# squall-blees-board.net
KiCad netlist of a schematic drawn in EAGLE
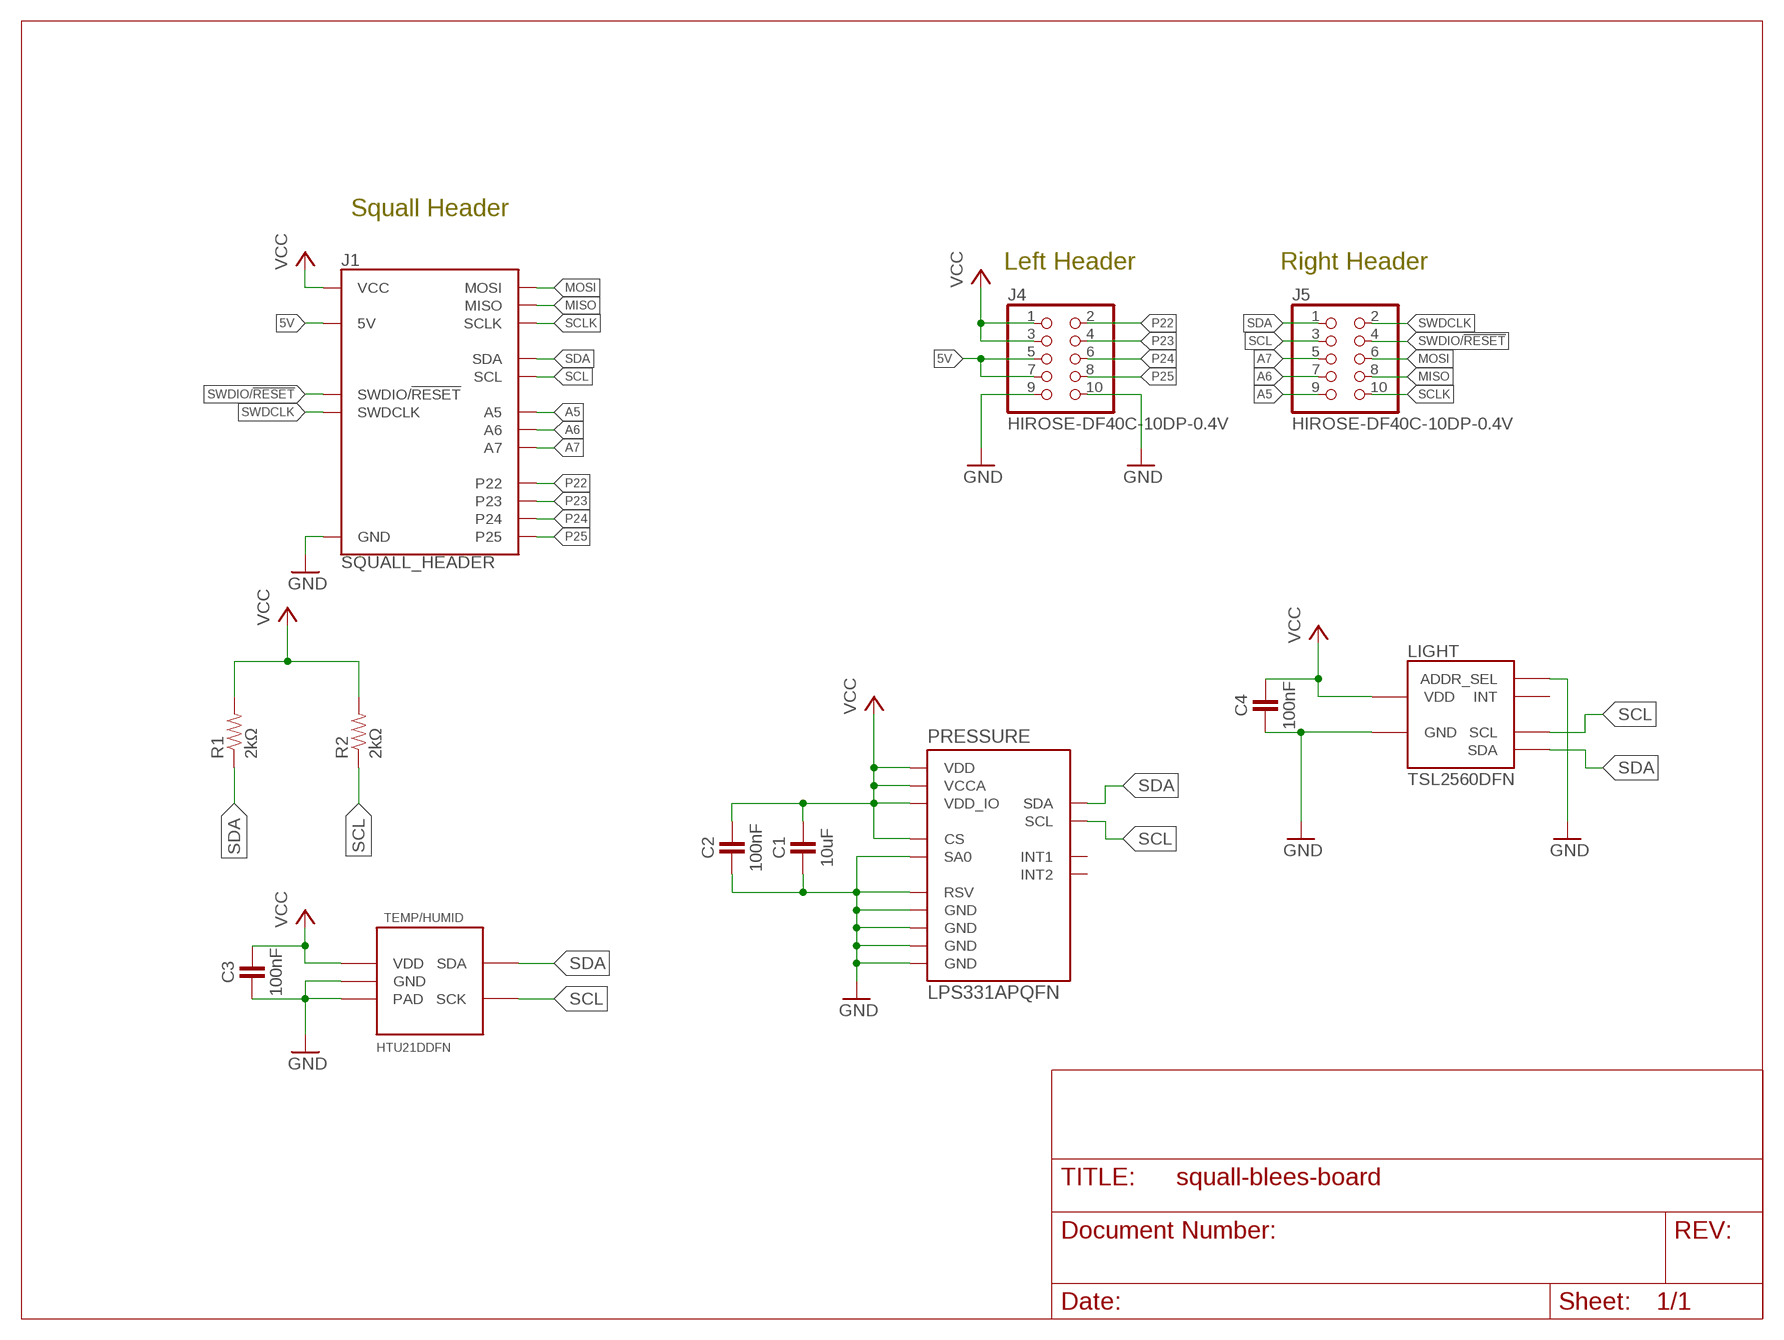
[diagram p0: schematic, sheet 1]

(export (version "E")
  (design (tool "Eeschema 10.0.6"))
  (components
    (comp (ref "C1")
      (value "10uF")
      (footprint "eagle-import:0603_CAP")
      (libsource (lib "eagle-import") (part "CAPACITOR0603_CAP"))
    )
    (comp (ref "C2")
      (value "100nF")
      (footprint "eagle-import:0402_CAP")
      (libsource (lib "eagle-import") (part "CAPACITOR"))
    )
    (comp (ref "C3")
      (value "100nF")
      (footprint "eagle-import:0402_CAP")
      (libsource (lib "eagle-import") (part "CAPACITOR"))
    )
    (comp (ref "C4")
      (value "100nF")
      (footprint "eagle-import:0402_CAP")
      (libsource (lib "eagle-import") (part "CAPACITOR"))
    )
    (comp (ref "J1")
      (value "SQUALL_HEADER")
      (footprint "eagle-import:SQUALL_HEADER")
      (libsource (lib "eagle-import") (part "SQUALL_HEADER"))
    )
    (comp (ref "J4")
      (value "HIROSE-DF40C-10DP-0.4V")
      (footprint "eagle-import:2X5_SMD_0.4MM")
      (libsource (lib "eagle-import") (part "HIROSE-DF40C-10DP-0.4V"))
    )
    (comp (ref "J5")
      (value "HIROSE-DF40C-10DP-0.4V")
      (footprint "eagle-import:2X5_SMD_0.4MM")
      (libsource (lib "eagle-import") (part "HIROSE-DF40C-10DP-0.4V"))
    )
    (comp (ref "LIGHT")
      (value "TSL2560DFN")
      (footprint "eagle-import:DFN2")
      (libsource (lib "eagle-import") (part "TSL2560DFN"))
    )
    (comp (ref "PRESSURE")
      (value "LPS331APQFN")
      (footprint "eagle-import:HCLGA-16L")
      (libsource (lib "eagle-import") (part "LPS331APQFN"))
    )
    (comp (ref "R1")
      (value "2kΩ")
      (footprint "eagle-import:0402_RES")
      (libsource (lib "eagle-import") (part "RESISTOR0402_RES"))
    )
    (comp (ref "R2")
      (value "2kΩ")
      (footprint "eagle-import:0402_RES")
      (libsource (lib "eagle-import") (part "RESISTOR0402_RES"))
    )
    (comp (ref "TEMP/HUMID")
      (value "HTU21DDFN")
      (footprint "eagle-import:DFN")
      (libsource (lib "eagle-import") (part "HTU21DDFN"))
    )
  )
  (nets
    (net (code "1") (name "/SWDIO{slash}~{RESET}") (class "Default")
      (node (ref "J1") (pin "B4") (pinfunction "SWDIO/~{RESET}_B4") (pintype "bidirectional"))
      (node (ref "J5") (pin "4") (pinfunction "4_4") (pintype "passive"))
    )
    (net (code "2") (name "5V") (class "Default")
      (node (ref "J1") (pin "A5") (pinfunction "5V_A5") (pintype "bidirectional"))
      (node (ref "J1") (pin "A7") (pinfunction "5V_A7") (pintype "bidirectional"))
      (node (ref "J4") (pin "5") (pinfunction "5_5") (pintype "passive"))
      (node (ref "J4") (pin "7") (pinfunction "7_7") (pintype "passive"))
    )
    (net (code "3") (name "A5") (class "Default")
      (node (ref "J1") (pin "B9") (pinfunction "A5_B9") (pintype "bidirectional"))
      (node (ref "J5") (pin "9") (pinfunction "9_9") (pintype "passive"))
    )
    (net (code "4") (name "A6") (class "Default")
      (node (ref "J1") (pin "B7") (pinfunction "A6_B7") (pintype "bidirectional"))
      (node (ref "J5") (pin "7") (pinfunction "7_7") (pintype "passive"))
    )
    (net (code "5") (name "A7") (class "Default")
      (node (ref "J1") (pin "B5") (pinfunction "A7_B5") (pintype "bidirectional"))
      (node (ref "J5") (pin "5") (pinfunction "5_5") (pintype "passive"))
    )
    (net (code "6") (name "GND") (class "Default")
      (node (ref "C1") (pin "2") (pinfunction "2_2") (pintype "bidirectional"))
      (node (ref "C2") (pin "2") (pinfunction "2_2") (pintype "bidirectional"))
      (node (ref "C3") (pin "2") (pinfunction "2_2") (pintype "bidirectional"))
      (node (ref "C4") (pin "2") (pinfunction "2_2") (pintype "bidirectional"))
      (node (ref "J1") (pin "A10") (pinfunction "GND_A10") (pintype "bidirectional"))
      (node (ref "J1") (pin "A9") (pinfunction "GND_A9") (pintype "bidirectional"))
      (node (ref "J4") (pin "10") (pinfunction "10_10") (pintype "passive"))
      (node (ref "J4") (pin "9") (pinfunction "9_9") (pintype "passive"))
      (node (ref "LIGHT") (pin "2") (pinfunction "ADDR_SEL_2") (pintype "bidirectional"))
      (node (ref "LIGHT") (pin "3") (pinfunction "GND_3") (pintype "power_in"))
      (node (ref "PRESSURE") (pin "10") (pinfunction "RSV_10") (pintype "power_in"))
      (node (ref "PRESSURE") (pin "12") (pinfunction "GND_12") (pintype "power_in"))
      (node (ref "PRESSURE") (pin "13") (pinfunction "GND_13") (pintype "power_in"))
      (node (ref "PRESSURE") (pin "16") (pinfunction "GND_16") (pintype "power_in"))
      (node (ref "PRESSURE") (pin "5") (pinfunction "GND_5") (pintype "power_in"))
      (node (ref "PRESSURE") (pin "7") (pinfunction "SA0_7") (pintype "input"))
      (node (ref "TEMP/HUMID") (pin "5") (pinfunction "GND_5") (pintype "power_in"))
      (node (ref "TEMP/HUMID") (pin "PAD") (pinfunction "PAD_PAD") (pintype "power_in"))
    )
    (net (code "7") (name "MISO") (class "Default")
      (node (ref "J1") (pin "B8") (pinfunction "MISO_B8") (pintype "bidirectional"))
      (node (ref "J5") (pin "8") (pinfunction "8_8") (pintype "passive"))
    )
    (net (code "8") (name "MOSI") (class "Default")
      (node (ref "J1") (pin "B6") (pinfunction "MOSI_B6") (pintype "bidirectional"))
      (node (ref "J5") (pin "6") (pinfunction "6_6") (pintype "passive"))
    )
    (net (code "9") (name "P22") (class "Default")
      (node (ref "J1") (pin "A2") (pinfunction "P22_A2") (pintype "bidirectional"))
      (node (ref "J4") (pin "2") (pinfunction "2_2") (pintype "passive"))
    )
    (net (code "10") (name "P23") (class "Default")
      (node (ref "J1") (pin "A4") (pinfunction "P23_A4") (pintype "bidirectional"))
      (node (ref "J4") (pin "4") (pinfunction "4_4") (pintype "passive"))
    )
    (net (code "11") (name "P24") (class "Default")
      (node (ref "J1") (pin "A6") (pinfunction "P24_A6") (pintype "bidirectional"))
      (node (ref "J4") (pin "6") (pinfunction "6_6") (pintype "passive"))
    )
    (net (code "12") (name "P25") (class "Default")
      (node (ref "J1") (pin "A8") (pinfunction "P25_A8") (pintype "bidirectional"))
      (node (ref "J4") (pin "8") (pinfunction "8_8") (pintype "passive"))
    )
    (net (code "13") (name "SCL") (class "Default")
      (node (ref "J1") (pin "B3") (pinfunction "SCL_B3") (pintype "bidirectional"))
      (node (ref "J5") (pin "3") (pinfunction "3_3") (pintype "passive"))
      (node (ref "LIGHT") (pin "4") (pinfunction "SCL_4") (pintype "bidirectional"))
      (node (ref "PRESSURE") (pin "4") (pinfunction "SCL_4") (pintype "bidirectional"))
      (node (ref "R2") (pin "1") (pinfunction "1_1") (pintype "passive"))
      (node (ref "TEMP/HUMID") (pin "1") (pinfunction "SCK_1") (pintype "bidirectional"))
    )
    (net (code "14") (name "SCLK") (class "Default")
      (node (ref "J1") (pin "B10") (pinfunction "SCLK_B10") (pintype "bidirectional"))
      (node (ref "J5") (pin "10") (pinfunction "10_10") (pintype "passive"))
    )
    (net (code "15") (name "SDA") (class "Default")
      (node (ref "J1") (pin "B1") (pinfunction "SDA_B1") (pintype "bidirectional"))
      (node (ref "J5") (pin "1") (pinfunction "1_1") (pintype "passive"))
      (node (ref "LIGHT") (pin "6") (pinfunction "SDA_6") (pintype "bidirectional"))
      (node (ref "PRESSURE") (pin "6") (pinfunction "SDA_6") (pintype "bidirectional"))
      (node (ref "R1") (pin "1") (pinfunction "1_1") (pintype "passive"))
      (node (ref "TEMP/HUMID") (pin "6") (pinfunction "SDA_6") (pintype "bidirectional"))
    )
    (net (code "16") (name "SWDCLK") (class "Default")
      (node (ref "J1") (pin "B2") (pinfunction "SWDCLK_B2") (pintype "bidirectional"))
      (node (ref "J5") (pin "2") (pinfunction "2_2") (pintype "passive"))
    )
    (net (code "17") (name "VCC") (class "Default")
      (node (ref "C1") (pin "1") (pinfunction "1_1") (pintype "bidirectional"))
      (node (ref "C2") (pin "1") (pinfunction "1_1") (pintype "bidirectional"))
      (node (ref "C3") (pin "1") (pinfunction "1_1") (pintype "bidirectional"))
      (node (ref "C4") (pin "1") (pinfunction "1_1") (pintype "bidirectional"))
      (node (ref "J1") (pin "A1") (pinfunction "VCC_A1") (pintype "bidirectional"))
      (node (ref "J1") (pin "A3") (pinfunction "VCC_A3") (pintype "bidirectional"))
      (node (ref "J4") (pin "1") (pinfunction "1_1") (pintype "passive"))
      (node (ref "J4") (pin "3") (pinfunction "3_3") (pintype "passive"))
      (node (ref "LIGHT") (pin "1") (pinfunction "VDD_1") (pintype "power_in"))
      (node (ref "PRESSURE") (pin "1") (pinfunction "VDD_IO_1") (pintype "power_in"))
      (node (ref "PRESSURE") (pin "14") (pinfunction "VDD_14") (pintype "power_in"))
      (node (ref "PRESSURE") (pin "15") (pinfunction "VCCA_15") (pintype "power_in"))
      (node (ref "PRESSURE") (pin "8") (pinfunction "CS_8") (pintype "input"))
      (node (ref "R1") (pin "2") (pinfunction "2_2") (pintype "passive"))
      (node (ref "R2") (pin "2") (pinfunction "2_2") (pintype "passive"))
      (node (ref "TEMP/HUMID") (pin "2") (pinfunction "VDD_2") (pintype "power_in"))
    )
    (net (code "18") (name "unconnected-(LIGHT-INT-Pad5)") (class "Default")
      (node (ref "LIGHT") (pin "5") (pinfunction "INT_5") (pintype "bidirectional"))
    )
    (net (code "19") (name "unconnected-(PRESSURE-INT1-Pad11)") (class "Default")
      (node (ref "PRESSURE") (pin "11") (pinfunction "INT1_11") (pintype "bidirectional"))
    )
    (net (code "20") (name "unconnected-(PRESSURE-INT2-Pad9)") (class "Default")
      (node (ref "PRESSURE") (pin "9") (pinfunction "INT2_9") (pintype "bidirectional"))
    )
  )
)
